# DAC.net
KiCad netlist of a schematic drawn in Altium Designer
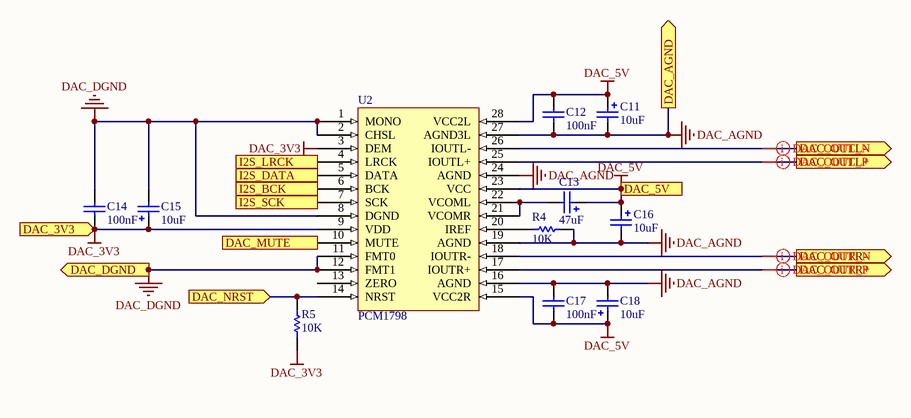
[diagram p0: DAC.SchDoc]

(export (version "E")
  (design (tool "Eeschema 10.0.6"))
  (components
    (comp (ref "C11")
      (value "10uF")
      (footprint "THT_Cap5x11")
      (libsource (lib "Common") (part "Cap Electrolyte"))
    )
    (comp (ref "C12") (value "100nF") (footprint "SMC_0402") (libsource (lib "Common") (part "Cap Ceramic")))
    (comp (ref "C13")
      (value "47uF")
      (footprint "THT_Cap5x11")
      (libsource (lib "Common") (part "Cap Electrolyte"))
    )
    (comp (ref "C14") (value "100nF") (footprint "SMC_0402") (libsource (lib "Common") (part "Cap Ceramic")))
    (comp (ref "C15")
      (value "10uF")
      (footprint "THT_Cap5x11")
      (libsource (lib "Common") (part "Cap Electrolyte"))
    )
    (comp (ref "C16")
      (value "10uF")
      (footprint "THT_Cap5x11")
      (libsource (lib "Common") (part "Cap Electrolyte"))
    )
    (comp (ref "C17") (value "100nF") (footprint "SMC_0402") (libsource (lib "Common") (part "Cap Ceramic")))
    (comp (ref "C18")
      (value "10uF")
      (footprint "THT_Cap5x11")
      (libsource (lib "Common") (part "Cap Electrolyte"))
    )
    (comp (ref "R4") (value "10K") (footprint "SMR_0402") (libsource (lib "Common") (part "Res SMT")))
    (comp (ref "R5") (value "10K") (footprint "SMR_0402") (libsource (lib "Common") (part "Res SMT")))
    (comp (ref "U2")
      (value "PCM1798")
      (footprint "SOP65P780X200-28N")
      (libsource (lib "Audio") (part "PCM1798"))
    )
  )
  (nets
    (net (code "1") (name "/DAC_MUTE") (class "Default")
      (node (ref "U2") (pin "10") (pinfunction "MUTE_10") (pintype "input"))
    )
    (net (code "2") (name "/DAC_NRST") (class "Default")
      (node (ref "R5") (pin "2") (pinfunction "2_2") (pintype "passive"))
      (node (ref "U2") (pin "14") (pinfunction "NRST_14") (pintype "input"))
    )
    (net (code "3") (name "/DAC_OUTL+") (class "Default")
      (node (ref "U2") (pin "25") (pinfunction "IOUTL+_25") (pintype "input"))
    )
    (net (code "4") (name "/DAC_OUTL-") (class "Default")
      (node (ref "U2") (pin "26") (pinfunction "IOUTL-_26") (pintype "input"))
    )
    (net (code "5") (name "/DAC_OUTR+") (class "Default")
      (node (ref "U2") (pin "17") (pinfunction "IOUTR+_17") (pintype "input"))
    )
    (net (code "6") (name "/DAC_OUTR-") (class "Default")
      (node (ref "U2") (pin "18") (pinfunction "IOUTR-_18") (pintype "input"))
    )
    (net (code "7") (name "/I2S_BCK") (class "Default")
      (node (ref "U2") (pin "6") (pinfunction "BCK_6") (pintype "input"))
    )
    (net (code "8") (name "/I2S_DATA") (class "Default")
      (node (ref "U2") (pin "5") (pinfunction "DATA_5") (pintype "input"))
    )
    (net (code "9") (name "/I2S_LRCK") (class "Default")
      (node (ref "U2") (pin "4") (pinfunction "LRCK_4") (pintype "input"))
    )
    (net (code "10") (name "/I2S_SCK") (class "Default")
      (node (ref "U2") (pin "7") (pinfunction "SCK_7") (pintype "input"))
    )
    (net (code "11") (name "DAC_3V3") (class "Default")
      (node (ref "C14") (pin "1") (pinfunction "1_1") (pintype "passive"))
      (node (ref "C15") (pin "A") (pinfunction "A_A") (pintype "passive"))
      (node (ref "R5") (pin "1") (pinfunction "1_1") (pintype "passive"))
      (node (ref "U2") (pin "3") (pinfunction "DEM_3") (pintype "input"))
      (node (ref "U2") (pin "9") (pinfunction "VDD_9") (pintype "input"))
    )
    (net (code "12") (name "DAC_5V") (class "Default")
      (node (ref "C11") (pin "A") (pinfunction "A_A") (pintype "passive"))
      (node (ref "C12") (pin "2") (pinfunction "2_2") (pintype "passive"))
      (node (ref "C13") (pin "A") (pinfunction "A_A") (pintype "passive"))
      (node (ref "C16") (pin "A") (pinfunction "A_A") (pintype "passive"))
      (node (ref "C17") (pin "2") (pinfunction "2_2") (pintype "passive"))
      (node (ref "C18") (pin "A") (pinfunction "A_A") (pintype "passive"))
      (node (ref "U2") (pin "15") (pinfunction "VCC2R_15") (pintype "input"))
      (node (ref "U2") (pin "23") (pinfunction "VCC_23") (pintype "input"))
      (node (ref "U2") (pin "28") (pinfunction "VCC2L_28") (pintype "input"))
    )
    (net (code "13") (name "DAC_AGND") (class "Default")
      (node (ref "C11") (pin "K") (pinfunction "K_K") (pintype "passive"))
      (node (ref "C12") (pin "1") (pinfunction "1_1") (pintype "passive"))
      (node (ref "C16") (pin "K") (pinfunction "K_K") (pintype "passive"))
      (node (ref "C17") (pin "1") (pinfunction "1_1") (pintype "passive"))
      (node (ref "C18") (pin "K") (pinfunction "K_K") (pintype "passive"))
      (node (ref "R4") (pin "2") (pinfunction "2_2") (pintype "passive"))
      (node (ref "U2") (pin "16") (pinfunction "AGND_16") (pintype "input"))
      (node (ref "U2") (pin "19") (pinfunction "AGND_19") (pintype "input"))
      (node (ref "U2") (pin "24") (pinfunction "AGND_24") (pintype "input"))
      (node (ref "U2") (pin "27") (pinfunction "AGND3L_27") (pintype "input"))
    )
    (net (code "14") (name "DAC_DGND") (class "Default")
      (node (ref "C14") (pin "2") (pinfunction "2_2") (pintype "passive"))
      (node (ref "C15") (pin "K") (pinfunction "K_K") (pintype "passive"))
      (node (ref "U2") (pin "1") (pinfunction "MONO_1") (pintype "input"))
      (node (ref "U2") (pin "11") (pinfunction "FMT0_11") (pintype "input"))
      (node (ref "U2") (pin "12") (pinfunction "FMT1_12") (pintype "input"))
      (node (ref "U2") (pin "2") (pinfunction "CHSL_2") (pintype "input"))
      (node (ref "U2") (pin "8") (pinfunction "DGND_8") (pintype "input"))
    )
    (net (code "15") (name "Net-(U2-IREF)") (class "Default")
      (node (ref "R4") (pin "1") (pinfunction "1_1") (pintype "passive"))
      (node (ref "U2") (pin "20") (pinfunction "IREF_20") (pintype "input"))
    )
    (net (code "16") (name "Net-(U2-VCOML)") (class "Default")
      (node (ref "C13") (pin "K") (pinfunction "K_K") (pintype "passive"))
      (node (ref "U2") (pin "21") (pinfunction "VCOMR_21") (pintype "input"))
      (node (ref "U2") (pin "22") (pinfunction "VCOML_22") (pintype "input"))
    )
    (net (code "17") (name "unconnected-(U2-ZERO-Pad13)") (class "Default")
      (node (ref "U2") (pin "13") (pinfunction "ZERO_13") (pintype "input"))
    )
  )
)
